# motor.net
KiCad netlist of a schematic drawn in EAGLE
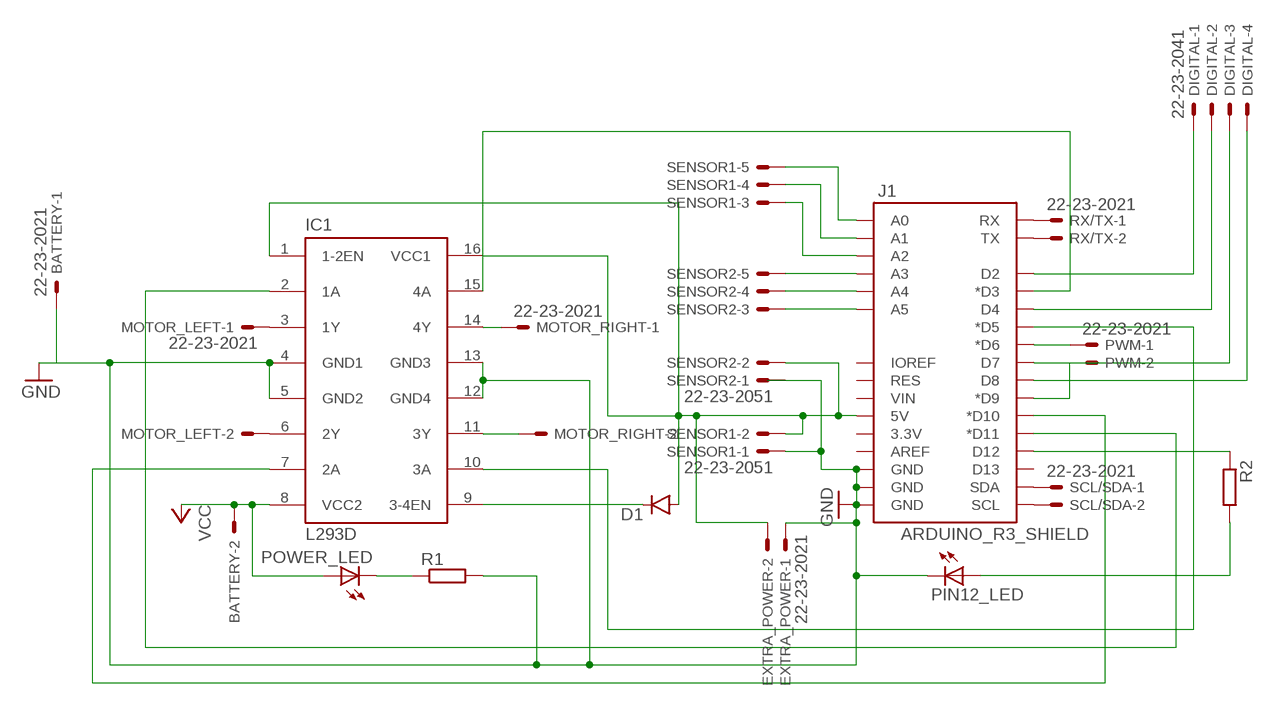
[diagram p0: schematic, sheet 1]

(export (version "E")
  (design (tool "Eeschema 10.0.6"))
  (components
    (comp (ref "BATTERY")
      (value "22-23-2021")
      (footprint "eagle-import:22-23-2021")
      (fields (field (name "MF") "MOLEX"))
      (libsource (lib "eagle-import") (part "22-23-2021"))
    )
    (comp (ref "D1")
      (value "DIODEPTH")
      (footprint "eagle-import:DIODE-1N4001")
      (libsource (lib "eagle-import") (part "DIODEPTH"))
    )
    (comp (ref "DIGITAL")
      (value "22-23-2041")
      (footprint "eagle-import:22-23-2041")
      (fields (field (name "MF") "MOLEX"))
      (libsource (lib "eagle-import") (part "22-23-2041"))
    )
    (comp (ref "EXTRA_POWER")
      (value "22-23-2021")
      (footprint "eagle-import:22-23-2021")
      (fields (field (name "MF") "MOLEX"))
      (libsource (lib "eagle-import") (part "22-23-2021"))
    )
    (comp (ref "IC1")
      (value "L293D")
      (footprint "eagle-import:DIL16")
      (libsource (lib "eagle-import") (part "L293D"))
    )
    (comp (ref "J1")
      (value "ARDUINO_R3_SHIELD")
      (footprint "eagle-import:UNO_R3_SHIELD")
      (libsource (lib "eagle-import") (part "ARDUINO_R3_SHIELD"))
    )
    (comp (ref "MOTOR_LEFT")
      (value "22-23-2021")
      (footprint "eagle-import:22-23-2021")
      (fields (field (name "MF") "MOLEX"))
      (libsource (lib "eagle-import") (part "22-23-2021"))
    )
    (comp (ref "MOTOR_RIGHT")
      (value "22-23-2021")
      (footprint "eagle-import:22-23-2021")
      (fields (field (name "MF") "MOLEX"))
      (libsource (lib "eagle-import") (part "22-23-2021"))
    )
    (comp (ref "PIN12_LED")
      (value "LEDSMT1206")
      (footprint "eagle-import:1206")
      (libsource (lib "eagle-import") (part "LEDSMT1206"))
    )
    (comp (ref "POWER_LED")
      (value "LEDSMT1206")
      (footprint "eagle-import:1206")
      (libsource (lib "eagle-import") (part "LEDSMT1206"))
    )
    (comp (ref "PWM")
      (value "22-23-2021")
      (footprint "eagle-import:22-23-2021")
      (fields (field (name "MF") "MOLEX"))
      (libsource (lib "eagle-import") (part "22-23-2021"))
    )
    (comp (ref "R1")
      (value "R-EU_R1206")
      (footprint "eagle-import:R1206")
      (libsource (lib "eagle-import") (part "R-EU_R1206"))
    )
    (comp (ref "R2")
      (value "R-EU_R1206")
      (footprint "eagle-import:R1206")
      (libsource (lib "eagle-import") (part "R-EU_R1206"))
    )
    (comp (ref "RX/TX")
      (value "22-23-2021")
      (footprint "eagle-import:22-23-2021")
      (fields (field (name "MF") "MOLEX"))
      (libsource (lib "eagle-import") (part "22-23-2021"))
    )
    (comp (ref "SCL/SDA")
      (value "22-23-2021")
      (footprint "eagle-import:22-23-2021")
      (fields (field (name "MF") "MOLEX"))
      (libsource (lib "eagle-import") (part "22-23-2021"))
    )
    (comp (ref "SENSOR1")
      (value "22-23-2051")
      (footprint "eagle-import:22-23-2051")
      (fields (field (name "MF") "MOLEX"))
      (libsource (lib "eagle-import") (part "22-23-2051"))
    )
    (comp (ref "SENSOR2")
      (value "22-23-2051")
      (footprint "eagle-import:22-23-2051")
      (fields (field (name "MF") "MOLEX"))
      (libsource (lib "eagle-import") (part "22-23-2051"))
    )
  )
  (nets
    (net (code "1") (name "GND") (class "Default")
      (node (ref "BATTERY") (pin "1") (pinfunction "S_1") (pintype "passive"))
      (node (ref "EXTRA_POWER") (pin "1") (pinfunction "S_1") (pintype "passive"))
      (node (ref "IC1") (pin "12") (pinfunction "GND4_12") (pintype "power_in"))
      (node (ref "IC1") (pin "13") (pinfunction "GND3_13") (pintype "power_in"))
      (node (ref "IC1") (pin "4") (pinfunction "GND1_4") (pintype "power_in"))
      (node (ref "IC1") (pin "5") (pinfunction "GND2_5") (pintype "power_in"))
      (node (ref "J1") (pin "GND@0") (pinfunction "GND_GND@0") (pintype "bidirectional"))
      (node (ref "J1") (pin "GND@1") (pinfunction "GND_GND@1") (pintype "bidirectional"))
      (node (ref "J1") (pin "GND@2") (pinfunction "GND_GND@2") (pintype "bidirectional"))
      (node (ref "PIN12_LED") (pin "C") (pinfunction "C_C") (pintype "passive"))
      (node (ref "R1") (pin "2") (pinfunction "2_2") (pintype "passive"))
      (node (ref "SENSOR1") (pin "1") (pinfunction "S_1") (pintype "passive"))
    )
    (net (code "2") (name "Net-(DIGITALA-S)") (class "Default")
      (node (ref "DIGITAL") (pin "1") (pinfunction "S_1") (pintype "passive"))
      (node (ref "J1") (pin "D2") (pinfunction "D2_D2") (pintype "bidirectional"))
    )
    (net (code "3") (name "Net-(DIGITALB-S)") (class "Default")
      (node (ref "DIGITAL") (pin "2") (pinfunction "S_2") (pintype "passive"))
      (node (ref "J1") (pin "D4") (pinfunction "D4_D4") (pintype "bidirectional"))
    )
    (net (code "4") (name "Net-(DIGITALC-S)") (class "Default")
      (node (ref "DIGITAL") (pin "3") (pinfunction "S_3") (pintype "passive"))
      (node (ref "J1") (pin "D7") (pinfunction "D7_D7") (pintype "bidirectional"))
    )
    (net (code "5") (name "Net-(DIGITALD-S)") (class "Default")
      (node (ref "DIGITAL") (pin "4") (pinfunction "S_4") (pintype "passive"))
      (node (ref "J1") (pin "D8") (pinfunction "D8_D8") (pintype "bidirectional"))
    )
    (net (code "6") (name "Net-(EXTRA_POWERB-S)") (class "Default")
      (node (ref "D1") (pin "A") (pinfunction "A_A") (pintype "passive"))
      (node (ref "EXTRA_POWER") (pin "2") (pinfunction "S_2") (pintype "passive"))
      (node (ref "IC1") (pin "1") (pinfunction "1-2EN_1") (pintype "input"))
      (node (ref "IC1") (pin "16") (pinfunction "VCC1_16") (pintype "power_in"))
      (node (ref "J1") (pin "5V") (pinfunction "5V_5V") (pintype "bidirectional"))
      (node (ref "SENSOR1") (pin "2") (pinfunction "S_2") (pintype "passive"))
      (node (ref "SENSOR2") (pin "2") (pinfunction "S_2") (pintype "passive"))
    )
    (net (code "7") (name "Net-(IC1-1A)") (class "Default")
      (node (ref "IC1") (pin "2") (pinfunction "1A_2") (pintype "input"))
      (node (ref "J1") (pin "D11") (pinfunction "*D11_D11") (pintype "bidirectional"))
    )
    (net (code "8") (name "Net-(IC1-1Y)") (class "Default")
      (node (ref "IC1") (pin "3") (pinfunction "1Y_3") (pintype "output"))
      (node (ref "MOTOR_LEFT") (pin "1") (pinfunction "S_1") (pintype "passive"))
    )
    (net (code "9") (name "Net-(IC1-2A)") (class "Default")
      (node (ref "IC1") (pin "7") (pinfunction "2A_7") (pintype "input"))
      (node (ref "J1") (pin "D10") (pinfunction "*D10_D10") (pintype "bidirectional"))
    )
    (net (code "10") (name "Net-(IC1-2Y)") (class "Default")
      (node (ref "IC1") (pin "6") (pinfunction "2Y_6") (pintype "output"))
      (node (ref "MOTOR_LEFT") (pin "2") (pinfunction "S_2") (pintype "passive"))
    )
    (net (code "11") (name "Net-(IC1-3-4EN)") (class "Default")
      (node (ref "D1") (pin "C") (pinfunction "C_C") (pintype "passive"))
      (node (ref "IC1") (pin "9") (pinfunction "3-4EN_9") (pintype "input"))
    )
    (net (code "12") (name "Net-(IC1-3A)") (class "Default")
      (node (ref "IC1") (pin "10") (pinfunction "3A_10") (pintype "input"))
      (node (ref "J1") (pin "D5") (pinfunction "*D5_D5") (pintype "bidirectional"))
    )
    (net (code "13") (name "Net-(IC1-3Y)") (class "Default")
      (node (ref "IC1") (pin "11") (pinfunction "3Y_11") (pintype "output"))
      (node (ref "MOTOR_RIGHT") (pin "2") (pinfunction "S_2") (pintype "passive"))
    )
    (net (code "14") (name "Net-(IC1-4A)") (class "Default")
      (node (ref "IC1") (pin "15") (pinfunction "4A_15") (pintype "input"))
      (node (ref "J1") (pin "D3") (pinfunction "*D3_D3") (pintype "bidirectional"))
    )
    (net (code "15") (name "Net-(IC1-4Y)") (class "Default")
      (node (ref "IC1") (pin "14") (pinfunction "4Y_14") (pintype "output"))
      (node (ref "MOTOR_RIGHT") (pin "1") (pinfunction "S_1") (pintype "passive"))
    )
    (net (code "16") (name "Net-(J1-*D6)") (class "Default")
      (node (ref "J1") (pin "D6") (pinfunction "*D6_D6") (pintype "bidirectional"))
      (node (ref "PWM") (pin "1") (pinfunction "S_1") (pintype "passive"))
    )
    (net (code "17") (name "Net-(J1-*D9)") (class "Default")
      (node (ref "J1") (pin "D9") (pinfunction "*D9_D9") (pintype "bidirectional"))
      (node (ref "PWM") (pin "2") (pinfunction "S_2") (pintype "passive"))
    )
    (net (code "18") (name "Net-(J1-PadD12)") (class "Default")
      (node (ref "J1") (pin "D12") (pinfunction "D12_D12") (pintype "bidirectional"))
      (node (ref "R2") (pin "1") (pinfunction "1_1") (pintype "passive"))
    )
    (net (code "19") (name "Net-(PIN12_LED-PadA)") (class "Default")
      (node (ref "PIN12_LED") (pin "A") (pinfunction "A_A") (pintype "passive"))
      (node (ref "R2") (pin "2") (pinfunction "2_2") (pintype "passive"))
    )
    (net (code "20") (name "Net-(POWER_LED-PadC)") (class "Default")
      (node (ref "POWER_LED") (pin "C") (pinfunction "C_C") (pintype "passive"))
      (node (ref "R1") (pin "1") (pinfunction "1_1") (pintype "passive"))
    )
    (net (code "21") (name "Net-(RX/TXA-S)") (class "Default")
      (node (ref "J1") (pin "RX") (pinfunction "RX_RX") (pintype "bidirectional"))
      (node (ref "RX/TX") (pin "1") (pinfunction "S_1") (pintype "passive"))
    )
    (net (code "22") (name "Net-(RX/TXB-S)") (class "Default")
      (node (ref "J1") (pin "TX") (pinfunction "TX_TX") (pintype "bidirectional"))
      (node (ref "RX/TX") (pin "2") (pinfunction "S_2") (pintype "passive"))
    )
    (net (code "23") (name "Net-(SCL/SDAA-S)") (class "Default")
      (node (ref "J1") (pin "SDA") (pinfunction "SDA_SDA") (pintype "bidirectional"))
      (node (ref "SCL/SDA") (pin "1") (pinfunction "S_1") (pintype "passive"))
    )
    (net (code "24") (name "Net-(SCL/SDAB-S)") (class "Default")
      (node (ref "J1") (pin "SCL") (pinfunction "SCL_SCL") (pintype "bidirectional"))
      (node (ref "SCL/SDA") (pin "2") (pinfunction "S_2") (pintype "passive"))
    )
    (net (code "25") (name "Net-(SENSOR1C-S)") (class "Default")
      (node (ref "J1") (pin "A2") (pinfunction "A2_A2") (pintype "bidirectional"))
      (node (ref "SENSOR1") (pin "3") (pinfunction "S_3") (pintype "passive"))
    )
    (net (code "26") (name "Net-(SENSOR1D-S)") (class "Default")
      (node (ref "J1") (pin "A1") (pinfunction "A1_A1") (pintype "bidirectional"))
      (node (ref "SENSOR1") (pin "4") (pinfunction "S_4") (pintype "passive"))
    )
    (net (code "27") (name "Net-(SENSOR1E-S)") (class "Default")
      (node (ref "J1") (pin "A0") (pinfunction "A0_A0") (pintype "bidirectional"))
      (node (ref "SENSOR1") (pin "5") (pinfunction "S_5") (pintype "passive"))
    )
    (net (code "28") (name "Net-(SENSOR2C-S)") (class "Default")
      (node (ref "J1") (pin "A5") (pinfunction "A5_A5") (pintype "bidirectional"))
      (node (ref "SENSOR2") (pin "3") (pinfunction "S_3") (pintype "passive"))
    )
    (net (code "29") (name "Net-(SENSOR2D-S)") (class "Default")
      (node (ref "J1") (pin "A4") (pinfunction "A4_A4") (pintype "bidirectional"))
      (node (ref "SENSOR2") (pin "4") (pinfunction "S_4") (pintype "passive"))
    )
    (net (code "30") (name "Net-(SENSOR2E-S)") (class "Default")
      (node (ref "J1") (pin "A3") (pinfunction "A3_A3") (pintype "bidirectional"))
      (node (ref "SENSOR2") (pin "5") (pinfunction "S_5") (pintype "passive"))
    )
    (net (code "31") (name "VCC") (class "Default")
      (node (ref "BATTERY") (pin "2") (pinfunction "S_2") (pintype "passive"))
      (node (ref "IC1") (pin "8") (pinfunction "VCC2_8") (pintype "power_in"))
      (node (ref "POWER_LED") (pin "A") (pinfunction "A_A") (pintype "passive"))
    )
    (net (code "32") (name "unconnected-(J1-Pad3.3V)") (class "Default")
      (node (ref "J1") (pin "3.3V") (pinfunction "3.3V_3.3V") (pintype "bidirectional"))
    )
    (net (code "33") (name "unconnected-(J1-PadAREF)") (class "Default")
      (node (ref "J1") (pin "AREF") (pinfunction "AREF_AREF") (pintype "bidirectional"))
    )
    (net (code "34") (name "unconnected-(J1-PadD13)") (class "Default")
      (node (ref "J1") (pin "D13") (pinfunction "D13_D13") (pintype "bidirectional"))
    )
    (net (code "35") (name "unconnected-(J1-PadIOREF)") (class "Default")
      (node (ref "J1") (pin "IOREF") (pinfunction "IOREF_IOREF") (pintype "bidirectional"))
    )
    (net (code "36") (name "unconnected-(J1-PadRES)") (class "Default")
      (node (ref "J1") (pin "RES") (pinfunction "RES_RES") (pintype "bidirectional"))
    )
    (net (code "37") (name "unconnected-(J1-PadVIN)") (class "Default")
      (node (ref "J1") (pin "VIN") (pinfunction "VIN_VIN") (pintype "bidirectional"))
    )
    (net (code "38") (name "unconnected-(SENSOR2A-S-Pad1)") (class "Default")
      (node (ref "SENSOR2") (pin "1") (pinfunction "S_1") (pintype "passive"))
    )
  )
)
